# CellCircuit.net
KiCad netlist of a schematic drawn in Altium Designer
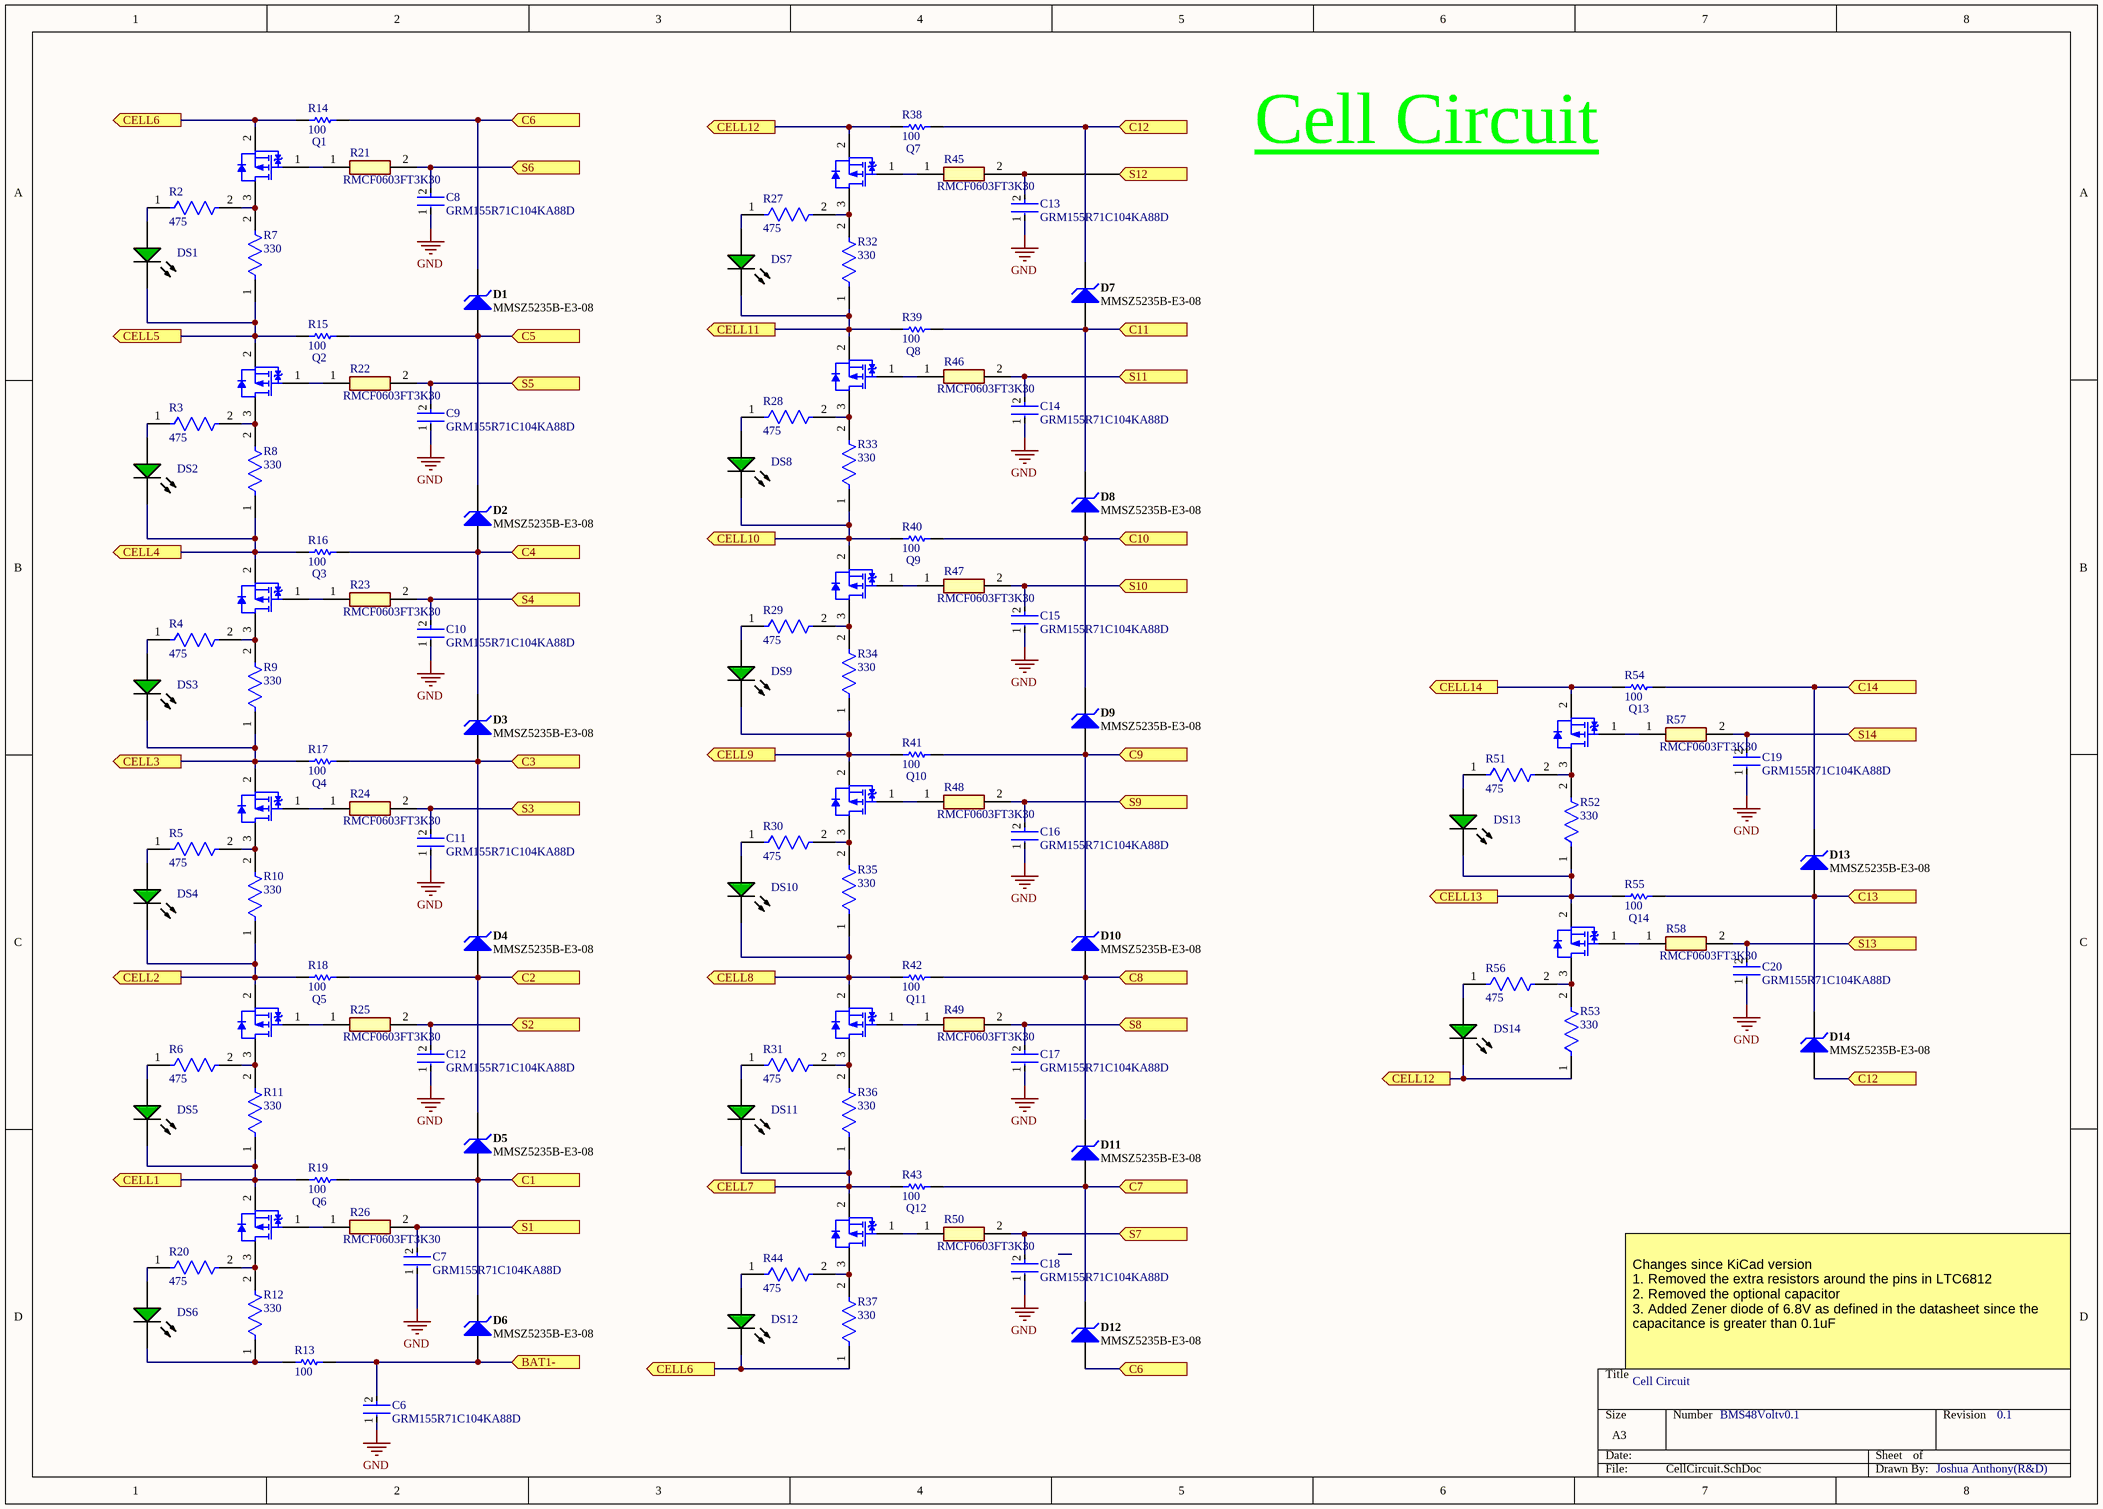
[diagram p0: CellCircuit.SchDoc]

(export (version "E")
  (design (tool "Eeschema 10.0.6"))
  (components
    (comp (ref "C6")
      (value "GRM155R71C104KA88D")
      (footprint "FP-GRM15-MFG")
      (description "CAP CER 0.1UF 16V X7R 0402")
      (fields
        (field (name "TOLERANCE") "10%")
        (field (name "OCTOPART") "https://octopart.com/grm155r71c104ka88d-murata-196880")
      )
      (libsource (lib "Altium Content Vault") (part "236180d848d6139a670b325ea6854c9"))
    )
    (comp (ref "C7")
      (value "GRM155R71C104KA88D")
      (footprint "FP-GRM15-MFG")
      (description "CAP CER 0.1UF 16V X7R 0402")
      (fields
        (field (name "TOLERANCE") "10%")
        (field (name "OCTOPART") "https://octopart.com/grm155r71c104ka88d-murata-196880")
      )
      (libsource (lib "Altium Content Vault") (part "236180d848d6139a670b325ea6854c9"))
    )
    (comp (ref "C8")
      (value "GRM155R71C104KA88D")
      (footprint "FP-GRM15-MFG")
      (description "CAP CER 0.1UF 16V X7R 0402")
      (fields
        (field (name "TOLERANCE") "10%")
        (field (name "OCTOPART") "https://octopart.com/grm155r71c104ka88d-murata-196880")
      )
      (libsource (lib "Altium Content Vault") (part "236180d848d6139a670b325ea6854c9"))
    )
    (comp (ref "C9")
      (value "GRM155R71C104KA88D")
      (footprint "FP-GRM15-MFG")
      (description "CAP CER 0.1UF 16V X7R 0402")
      (fields
        (field (name "TOLERANCE") "10%")
        (field (name "OCTOPART") "https://octopart.com/grm155r71c104ka88d-murata-196880")
      )
      (libsource (lib "Altium Content Vault") (part "236180d848d6139a670b325ea6854c9"))
    )
    (comp (ref "C10")
      (value "GRM155R71C104KA88D")
      (footprint "FP-GRM15-MFG")
      (description "CAP CER 0.1UF 16V X7R 0402")
      (fields
        (field (name "TOLERANCE") "10%")
        (field (name "OCTOPART") "https://octopart.com/grm155r71c104ka88d-murata-196880")
      )
      (libsource (lib "Altium Content Vault") (part "236180d848d6139a670b325ea6854c9"))
    )
    (comp (ref "C11")
      (value "GRM155R71C104KA88D")
      (footprint "FP-GRM15-MFG")
      (description "CAP CER 0.1UF 16V X7R 0402")
      (fields
        (field (name "TOLERANCE") "10%")
        (field (name "OCTOPART") "https://octopart.com/grm155r71c104ka88d-murata-196880")
      )
      (libsource (lib "Altium Content Vault") (part "236180d848d6139a670b325ea6854c9"))
    )
    (comp (ref "C12")
      (value "GRM155R71C104KA88D")
      (footprint "FP-GRM15-MFG")
      (description "CAP CER 0.1UF 16V X7R 0402")
      (fields
        (field (name "TOLERANCE") "10%")
        (field (name "OCTOPART") "https://octopart.com/grm155r71c104ka88d-murata-196880")
      )
      (libsource (lib "Altium Content Vault") (part "236180d848d6139a670b325ea6854c9"))
    )
    (comp (ref "C13")
      (value "GRM155R71C104KA88D")
      (footprint "FP-GRM15-MFG")
      (description "CAP CER 0.1UF 16V X7R 0402")
      (fields
        (field (name "TOLERANCE") "10%")
        (field (name "OCTOPART") "https://octopart.com/grm155r71c104ka88d-murata-196880")
      )
      (libsource (lib "Altium Content Vault") (part "236180d848d6139a670b325ea6854c9"))
    )
    (comp (ref "C14")
      (value "GRM155R71C104KA88D")
      (footprint "FP-GRM15-MFG")
      (description "CAP CER 0.1UF 16V X7R 0402")
      (fields
        (field (name "TOLERANCE") "10%")
        (field (name "OCTOPART") "https://octopart.com/grm155r71c104ka88d-murata-196880")
      )
      (libsource (lib "Altium Content Vault") (part "236180d848d6139a670b325ea6854c9"))
    )
    (comp (ref "C15")
      (value "GRM155R71C104KA88D")
      (footprint "FP-GRM15-MFG")
      (description "CAP CER 0.1UF 16V X7R 0402")
      (fields
        (field (name "TOLERANCE") "10%")
        (field (name "OCTOPART") "https://octopart.com/grm155r71c104ka88d-murata-196880")
      )
      (libsource (lib "Altium Content Vault") (part "236180d848d6139a670b325ea6854c9"))
    )
    (comp (ref "C16")
      (value "GRM155R71C104KA88D")
      (footprint "FP-GRM15-MFG")
      (description "CAP CER 0.1UF 16V X7R 0402")
      (fields
        (field (name "TOLERANCE") "10%")
        (field (name "OCTOPART") "https://octopart.com/grm155r71c104ka88d-murata-196880")
      )
      (libsource (lib "Altium Content Vault") (part "236180d848d6139a670b325ea6854c9"))
    )
    (comp (ref "C17")
      (value "GRM155R71C104KA88D")
      (footprint "FP-GRM15-MFG")
      (description "CAP CER 0.1UF 16V X7R 0402")
      (fields
        (field (name "TOLERANCE") "10%")
        (field (name "OCTOPART") "https://octopart.com/grm155r71c104ka88d-murata-196880")
      )
      (libsource (lib "Altium Content Vault") (part "236180d848d6139a670b325ea6854c9"))
    )
    (comp (ref "C18")
      (value "GRM155R71C104KA88D")
      (footprint "FP-GRM15-MFG")
      (description "CAP CER 0.1UF 16V X7R 0402")
      (fields
        (field (name "TOLERANCE") "10%")
        (field (name "OCTOPART") "https://octopart.com/grm155r71c104ka88d-murata-196880")
      )
      (libsource (lib "Altium Content Vault") (part "236180d848d6139a670b325ea6854c9"))
    )
    (comp (ref "C19")
      (value "GRM155R71C104KA88D")
      (footprint "FP-GRM15-MFG")
      (description "CAP CER 0.1UF 16V X7R 0402")
      (fields
        (field (name "TOLERANCE") "10%")
        (field (name "OCTOPART") "https://octopart.com/grm155r71c104ka88d-murata-196880")
      )
      (libsource (lib "Altium Content Vault") (part "236180d848d6139a670b325ea6854c9"))
    )
    (comp (ref "C20")
      (value "GRM155R71C104KA88D")
      (footprint "FP-GRM15-MFG")
      (description "CAP CER 0.1UF 16V X7R 0402")
      (fields
        (field (name "TOLERANCE") "10%")
        (field (name "OCTOPART") "https://octopart.com/grm155r71c104ka88d-murata-196880")
      )
      (libsource (lib "Altium Content Vault") (part "236180d848d6139a670b325ea6854c9"))
    )
    (comp (ref "D1")
      (value "MMSZ5235B-E3-08")
      (footprint "VISH-SOD-123-2_V")
      (description "Small Signal Zener Diode, 6.8 V +/- 5%, -55 to 155 degC, 2-Pin SOD-123, RoHS, Tape and Reel")
      (fields (field (name "MANUFACTURER") "Vishay Semiconductor") (field (name "TOLERANCE") "+/- 5%"))
      (libsource (lib "Altium Content Vault") (part "VISH-DZEN_A1K2-2"))
    )
    (comp (ref "D2")
      (value "MMSZ5235B-E3-08")
      (footprint "VISH-SOD-123-2_V")
      (description "Small Signal Zener Diode, 6.8 V +/- 5%, -55 to 155 degC, 2-Pin SOD-123, RoHS, Tape and Reel")
      (fields (field (name "MANUFACTURER") "Vishay Semiconductor") (field (name "TOLERANCE") "+/- 5%"))
      (libsource (lib "Altium Content Vault") (part "VISH-DZEN_A1K2-2"))
    )
    (comp (ref "D3")
      (value "MMSZ5235B-E3-08")
      (footprint "VISH-SOD-123-2_V")
      (description "Small Signal Zener Diode, 6.8 V +/- 5%, -55 to 155 degC, 2-Pin SOD-123, RoHS, Tape and Reel")
      (fields (field (name "MANUFACTURER") "Vishay Semiconductor") (field (name "TOLERANCE") "+/- 5%"))
      (libsource (lib "Altium Content Vault") (part "VISH-DZEN_A1K2-2"))
    )
    (comp (ref "D4")
      (value "MMSZ5235B-E3-08")
      (footprint "VISH-SOD-123-2_V")
      (description "Small Signal Zener Diode, 6.8 V +/- 5%, -55 to 155 degC, 2-Pin SOD-123, RoHS, Tape and Reel")
      (fields (field (name "MANUFACTURER") "Vishay Semiconductor") (field (name "TOLERANCE") "+/- 5%"))
      (libsource (lib "Altium Content Vault") (part "VISH-DZEN_A1K2-2"))
    )
    (comp (ref "D5")
      (value "MMSZ5235B-E3-08")
      (footprint "VISH-SOD-123-2_V")
      (description "Small Signal Zener Diode, 6.8 V +/- 5%, -55 to 155 degC, 2-Pin SOD-123, RoHS, Tape and Reel")
      (fields (field (name "MANUFACTURER") "Vishay Semiconductor") (field (name "TOLERANCE") "+/- 5%"))
      (libsource (lib "Altium Content Vault") (part "VISH-DZEN_A1K2-2"))
    )
    (comp (ref "D6")
      (value "MMSZ5235B-E3-08")
      (footprint "VISH-SOD-123-2_V")
      (description "Small Signal Zener Diode, 6.8 V +/- 5%, -55 to 155 degC, 2-Pin SOD-123, RoHS, Tape and Reel")
      (fields (field (name "MANUFACTURER") "Vishay Semiconductor") (field (name "TOLERANCE") "+/- 5%"))
      (libsource (lib "Altium Content Vault") (part "VISH-DZEN_A1K2-2"))
    )
    (comp (ref "D7")
      (value "MMSZ5235B-E3-08")
      (footprint "VISH-SOD-123-2_V")
      (description "Small Signal Zener Diode, 6.8 V +/- 5%, -55 to 155 degC, 2-Pin SOD-123, RoHS, Tape and Reel")
      (fields (field (name "MANUFACTURER") "Vishay Semiconductor") (field (name "TOLERANCE") "+/- 5%"))
      (libsource (lib "Altium Content Vault") (part "VISH-DZEN_A1K2-2"))
    )
    (comp (ref "D8")
      (value "MMSZ5235B-E3-08")
      (footprint "VISH-SOD-123-2_V")
      (description "Small Signal Zener Diode, 6.8 V +/- 5%, -55 to 155 degC, 2-Pin SOD-123, RoHS, Tape and Reel")
      (fields (field (name "MANUFACTURER") "Vishay Semiconductor") (field (name "TOLERANCE") "+/- 5%"))
      (libsource (lib "Altium Content Vault") (part "VISH-DZEN_A1K2-2"))
    )
    (comp (ref "D9")
      (value "MMSZ5235B-E3-08")
      (footprint "VISH-SOD-123-2_V")
      (description "Small Signal Zener Diode, 6.8 V +/- 5%, -55 to 155 degC, 2-Pin SOD-123, RoHS, Tape and Reel")
      (fields (field (name "MANUFACTURER") "Vishay Semiconductor") (field (name "TOLERANCE") "+/- 5%"))
      (libsource (lib "Altium Content Vault") (part "VISH-DZEN_A1K2-2"))
    )
    (comp (ref "D10")
      (value "MMSZ5235B-E3-08")
      (footprint "VISH-SOD-123-2_V")
      (description "Small Signal Zener Diode, 6.8 V +/- 5%, -55 to 155 degC, 2-Pin SOD-123, RoHS, Tape and Reel")
      (fields (field (name "MANUFACTURER") "Vishay Semiconductor") (field (name "TOLERANCE") "+/- 5%"))
      (libsource (lib "Altium Content Vault") (part "VISH-DZEN_A1K2-2"))
    )
    (comp (ref "D11")
      (value "MMSZ5235B-E3-08")
      (footprint "VISH-SOD-123-2_V")
      (description "Small Signal Zener Diode, 6.8 V +/- 5%, -55 to 155 degC, 2-Pin SOD-123, RoHS, Tape and Reel")
      (fields (field (name "MANUFACTURER") "Vishay Semiconductor") (field (name "TOLERANCE") "+/- 5%"))
      (libsource (lib "Altium Content Vault") (part "VISH-DZEN_A1K2-2"))
    )
    (comp (ref "D12")
      (value "MMSZ5235B-E3-08")
      (footprint "VISH-SOD-123-2_V")
      (description "Small Signal Zener Diode, 6.8 V +/- 5%, -55 to 155 degC, 2-Pin SOD-123, RoHS, Tape and Reel")
      (fields (field (name "MANUFACTURER") "Vishay Semiconductor") (field (name "TOLERANCE") "+/- 5%"))
      (libsource (lib "Altium Content Vault") (part "VISH-DZEN_A1K2-2"))
    )
    (comp (ref "D13")
      (value "MMSZ5235B-E3-08")
      (footprint "VISH-SOD-123-2_V")
      (description "Small Signal Zener Diode, 6.8 V +/- 5%, -55 to 155 degC, 2-Pin SOD-123, RoHS, Tape and Reel")
      (fields (field (name "MANUFACTURER") "Vishay Semiconductor") (field (name "TOLERANCE") "+/- 5%"))
      (libsource (lib "Altium Content Vault") (part "VISH-DZEN_A1K2-2"))
    )
    (comp (ref "D14")
      (value "MMSZ5235B-E3-08")
      (footprint "VISH-SOD-123-2_V")
      (description "Small Signal Zener Diode, 6.8 V +/- 5%, -55 to 155 degC, 2-Pin SOD-123, RoHS, Tape and Reel")
      (fields (field (name "MANUFACTURER") "Vishay Semiconductor") (field (name "TOLERANCE") "+/- 5%"))
      (libsource (lib "Altium Content Vault") (part "VISH-DZEN_A1K2-2"))
    )
    (comp (ref "DS1")
      (value "HSMG-C170")
      (footprint "AVAG-HSMX-C170_V")
      (description "Chip LED, Green, 2.2 V, -40 to 85 degC, 2-Pin SMD, Pb-Free, Tape and Reel")
      (fields (field (name "MANUFACTURER") "Avago"))
      (libsource (lib "Altium Content Vault") (part "LED_GREEN_A1K2-2"))
    )
    (comp (ref "DS2")
      (value "HSMG-C170")
      (footprint "AVAG-HSMX-C170_V")
      (description "Chip LED, Green, 2.2 V, -40 to 85 degC, 2-Pin SMD, Pb-Free, Tape and Reel")
      (fields (field (name "MANUFACTURER") "Avago"))
      (libsource (lib "Altium Content Vault") (part "LED_GREEN_A1K2-2"))
    )
    (comp (ref "DS3")
      (value "HSMG-C170")
      (footprint "AVAG-HSMX-C170_V")
      (description "Chip LED, Green, 2.2 V, -40 to 85 degC, 2-Pin SMD, Pb-Free, Tape and Reel")
      (fields (field (name "MANUFACTURER") "Avago"))
      (libsource (lib "Altium Content Vault") (part "LED_GREEN_A1K2-2"))
    )
    (comp (ref "DS4")
      (value "HSMG-C170")
      (footprint "AVAG-HSMX-C170_V")
      (description "Chip LED, Green, 2.2 V, -40 to 85 degC, 2-Pin SMD, Pb-Free, Tape and Reel")
      (fields (field (name "MANUFACTURER") "Avago"))
      (libsource (lib "Altium Content Vault") (part "LED_GREEN_A1K2-2"))
    )
    (comp (ref "DS5")
      (value "HSMG-C170")
      (footprint "AVAG-HSMX-C170_V")
      (description "Chip LED, Green, 2.2 V, -40 to 85 degC, 2-Pin SMD, Pb-Free, Tape and Reel")
      (fields (field (name "MANUFACTURER") "Avago"))
      (libsource (lib "Altium Content Vault") (part "LED_GREEN_A1K2-2"))
    )
    (comp (ref "DS6")
      (value "HSMG-C170")
      (footprint "AVAG-HSMX-C170_V")
      (description "Chip LED, Green, 2.2 V, -40 to 85 degC, 2-Pin SMD, Pb-Free, Tape and Reel")
      (fields (field (name "MANUFACTURER") "Avago"))
      (libsource (lib "Altium Content Vault") (part "LED_GREEN_A1K2-2"))
    )
    (comp (ref "DS7")
      (value "HSMG-C170")
      (footprint "AVAG-HSMX-C170_V")
      (description "Chip LED, Green, 2.2 V, -40 to 85 degC, 2-Pin SMD, Pb-Free, Tape and Reel")
      (fields (field (name "MANUFACTURER") "Avago"))
      (libsource (lib "Altium Content Vault") (part "LED_GREEN_A1K2-2"))
    )
    (comp (ref "DS8")
      (value "HSMG-C170")
      (footprint "AVAG-HSMX-C170_V")
      (description "Chip LED, Green, 2.2 V, -40 to 85 degC, 2-Pin SMD, Pb-Free, Tape and Reel")
      (fields (field (name "MANUFACTURER") "Avago"))
      (libsource (lib "Altium Content Vault") (part "LED_GREEN_A1K2-2"))
    )
    (comp (ref "DS9")
      (value "HSMG-C170")
      (footprint "AVAG-HSMX-C170_V")
      (description "Chip LED, Green, 2.2 V, -40 to 85 degC, 2-Pin SMD, Pb-Free, Tape and Reel")
      (fields (field (name "MANUFACTURER") "Avago"))
      (libsource (lib "Altium Content Vault") (part "LED_GREEN_A1K2-2"))
    )
    (comp (ref "DS10")
      (value "HSMG-C170")
      (footprint "AVAG-HSMX-C170_V")
      (description "Chip LED, Green, 2.2 V, -40 to 85 degC, 2-Pin SMD, Pb-Free, Tape and Reel")
      (fields (field (name "MANUFACTURER") "Avago"))
      (libsource (lib "Altium Content Vault") (part "LED_GREEN_A1K2-2"))
    )
    (comp (ref "DS11")
      (value "HSMG-C170")
      (footprint "AVAG-HSMX-C170_V")
      (description "Chip LED, Green, 2.2 V, -40 to 85 degC, 2-Pin SMD, Pb-Free, Tape and Reel")
      (fields (field (name "MANUFACTURER") "Avago"))
      (libsource (lib "Altium Content Vault") (part "LED_GREEN_A1K2-2"))
    )
    (comp (ref "DS12")
      (value "HSMG-C170")
      (footprint "AVAG-HSMX-C170_V")
      (description "Chip LED, Green, 2.2 V, -40 to 85 degC, 2-Pin SMD, Pb-Free, Tape and Reel")
      (fields (field (name "MANUFACTURER") "Avago"))
      (libsource (lib "Altium Content Vault") (part "LED_GREEN_A1K2-2"))
    )
    (comp (ref "DS13")
      (value "HSMG-C170")
      (footprint "AVAG-HSMX-C170_V")
      (description "Chip LED, Green, 2.2 V, -40 to 85 degC, 2-Pin SMD, Pb-Free, Tape and Reel")
      (fields (field (name "MANUFACTURER") "Avago"))
      (libsource (lib "Altium Content Vault") (part "LED_GREEN_A1K2-2"))
    )
    (comp (ref "DS14")
      (value "HSMG-C170")
      (footprint "AVAG-HSMX-C170_V")
      (description "Chip LED, Green, 2.2 V, -40 to 85 degC, 2-Pin SMD, Pb-Free, Tape and Reel")
      (fields (field (name "MANUFACTURER") "Avago"))
      (libsource (lib "Altium Content Vault") (part "LED_GREEN_A1K2-2"))
    )
    (comp (ref "Q1")
      (value "BSS308PE")
      (footprint "INF-PG-SOT23_L")
      (fields (field (name "MANUFACTURER") "Infineon"))
      (libsource (lib "Altium Content Vault") (part "INF-BSS3XXPE-PG-SOT23-3"))
    )
    (comp (ref "Q2")
      (value "BSS308PE")
      (footprint "INF-PG-SOT23_L")
      (fields (field (name "MANUFACTURER") "Infineon"))
      (libsource (lib "Altium Content Vault") (part "INF-BSS3XXPE-PG-SOT23-3"))
    )
    (comp (ref "Q3")
      (value "BSS308PE")
      (footprint "INF-PG-SOT23_L")
      (fields (field (name "MANUFACTURER") "Infineon"))
      (libsource (lib "Altium Content Vault") (part "INF-BSS3XXPE-PG-SOT23-3"))
    )
    (comp (ref "Q4")
      (value "BSS308PE")
      (footprint "INF-PG-SOT23_L")
      (fields (field (name "MANUFACTURER") "Infineon"))
      (libsource (lib "Altium Content Vault") (part "INF-BSS3XXPE-PG-SOT23-3"))
    )
    (comp (ref "Q5")
      (value "BSS308PE")
      (footprint "INF-PG-SOT23_L")
      (fields (field (name "MANUFACTURER") "Infineon"))
      (libsource (lib "Altium Content Vault") (part "INF-BSS3XXPE-PG-SOT23-3"))
    )
    (comp (ref "Q6")
      (value "BSS308PE")
      (footprint "INF-PG-SOT23_L")
      (fields (field (name "MANUFACTURER") "Infineon"))
      (libsource (lib "Altium Content Vault") (part "INF-BSS3XXPE-PG-SOT23-3"))
    )
    (comp (ref "Q7")
      (value "BSS308PE")
      (footprint "INF-PG-SOT23_L")
      (fields (field (name "MANUFACTURER") "Infineon"))
      (libsource (lib "Altium Content Vault") (part "INF-BSS3XXPE-PG-SOT23-3"))
    )
    (comp (ref "Q8")
      (value "BSS308PE")
      (footprint "INF-PG-SOT23_L")
      (fields (field (name "MANUFACTURER") "Infineon"))
      (libsource (lib "Altium Content Vault") (part "INF-BSS3XXPE-PG-SOT23-3"))
    )
    (comp (ref "Q9")
      (value "BSS308PE")
      (footprint "INF-PG-SOT23_L")
      (fields (field (name "MANUFACTURER") "Infineon"))
      (libsource (lib "Altium Content Vault") (part "INF-BSS3XXPE-PG-SOT23-3"))
    )
    (comp (ref "Q10")
      (value "BSS308PE")
      (footprint "INF-PG-SOT23_L")
      (fields (field (name "MANUFACTURER") "Infineon"))
      (libsource (lib "Altium Content Vault") (part "INF-BSS3XXPE-PG-SOT23-3"))
    )
    (comp (ref "Q11")
      (value "BSS308PE")
      (footprint "INF-PG-SOT23_L")
      (fields (field (name "MANUFACTURER") "Infineon"))
      (libsource (lib "Altium Content Vault") (part "INF-BSS3XXPE-PG-SOT23-3"))
    )
    (comp (ref "Q12")
      (value "BSS308PE")
      (footprint "INF-PG-SOT23_L")
      (fields (field (name "MANUFACTURER") "Infineon"))
      (libsource (lib "Altium Content Vault") (part "INF-BSS3XXPE-PG-SOT23-3"))
    )
    (comp (ref "Q13")
      (value "BSS308PE")
      (footprint "INF-PG-SOT23_L")
      (fields (field (name "MANUFACTURER") "Infineon"))
      (libsource (lib "Altium Content Vault") (part "INF-BSS3XXPE-PG-SOT23-3"))
    )
    (comp (ref "Q14")
      (value "BSS308PE")
      (footprint "INF-PG-SOT23_L")
      (fields (field (name "MANUFACTURER") "Infineon"))
      (libsource (lib "Altium Content Vault") (part "INF-BSS3XXPE-PG-SOT23-3"))
    )
    (comp (ref "R2")
      (value "475")
      (footprint "FP-CR0603-MFG")
      (description "Thick Film Chip Resistors 0603 475Ω 0.1W 1% 100ppm/°C")
      (fields (field (name "TOLERANCE") "1%"))
      (libsource (lib "Altium Content Vault") (part "1029c3af85768c4190bb7ad29bc67b5"))
    )
    (comp (ref "R3")
      (value "475")
      (footprint "FP-CR0603-MFG")
      (description "Thick Film Chip Resistors 0603 475Ω 0.1W 1% 100ppm/°C")
      (fields (field (name "TOLERANCE") "1%"))
      (libsource (lib "Altium Content Vault") (part "1029c3af85768c4190bb7ad29bc67b5"))
    )
    (comp (ref "R4")
      (value "475")
      (footprint "FP-CR0603-MFG")
      (description "Thick Film Chip Resistors 0603 475Ω 0.1W 1% 100ppm/°C")
      (fields (field (name "TOLERANCE") "1%"))
      (libsource (lib "Altium Content Vault") (part "1029c3af85768c4190bb7ad29bc67b5"))
    )
    (comp (ref "R5")
      (value "475")
      (footprint "FP-CR0603-MFG")
      (description "Thick Film Chip Resistors 0603 475Ω 0.1W 1% 100ppm/°C")
      (fields (field (name "TOLERANCE") "1%"))
      (libsource (lib "Altium Content Vault") (part "1029c3af85768c4190bb7ad29bc67b5"))
    )
    (comp (ref "R6")
      (value "475")
      (footprint "FP-CR0603-MFG")
      (description "Thick Film Chip Resistors 0603 475Ω 0.1W 1% 100ppm/°C")
      (fields (field (name "TOLERANCE") "1%"))
      (libsource (lib "Altium Content Vault") (part "1029c3af85768c4190bb7ad29bc67b5"))
    )
    (comp (ref "R7")
      (value "330")
      (footprint "FP-CRCW0603-e3-MFG")
      (description "RES Thick Film, 330Ω, 1%, 0.1W, 100ppm/°C, 0603")
      (fields (field (name "TOLERANCE") "1%"))
      (libsource (lib "Altium Content Vault") (part "1029c3af85768c4190bb7ad29bc67b5"))
    )
    (comp (ref "R8")
      (value "330")
      (footprint "FP-CRCW0603-e3-MFG")
      (description "RES Thick Film, 330Ω, 1%, 0.1W, 100ppm/°C, 0603")
      (fields (field (name "TOLERANCE") "1%"))
      (libsource (lib "Altium Content Vault") (part "1029c3af85768c4190bb7ad29bc67b5"))
    )
    (comp (ref "R9")
      (value "330")
      (footprint "FP-CRCW0603-e3-MFG")
      (description "RES Thick Film, 330Ω, 1%, 0.1W, 100ppm/°C, 0603")
      (fields (field (name "TOLERANCE") "1%"))
      (libsource (lib "Altium Content Vault") (part "1029c3af85768c4190bb7ad29bc67b5"))
    )
    (comp (ref "R10")
      (value "330")
      (footprint "FP-CRCW0603-e3-MFG")
      (description "RES Thick Film, 330Ω, 1%, 0.1W, 100ppm/°C, 0603")
      (fields (field (name "TOLERANCE") "1%"))
      (libsource (lib "Altium Content Vault") (part "1029c3af85768c4190bb7ad29bc67b5"))
    )
    (comp (ref "R11")
      (value "330")
      (footprint "FP-CRCW0603-e3-MFG")
      (description "RES Thick Film, 330Ω, 1%, 0.1W, 100ppm/°C, 0603")
      (fields (field (name "TOLERANCE") "1%"))
      (libsource (lib "Altium Content Vault") (part "1029c3af85768c4190bb7ad29bc67b5"))
    )
    (comp (ref "R12")
      (value "330")
      (footprint "FP-CRCW0603-e3-MFG")
      (description "RES Thick Film, 330Ω, 1%, 0.1W, 100ppm/°C, 0603")
      (fields (field (name "TOLERANCE") "1%"))
      (libsource (lib "Altium Content Vault") (part "1029c3af85768c4190bb7ad29bc67b5"))
    )
    (comp (ref "R13")
      (value "100")
      (footprint "RESC1005X40X25LL05T05")
      (description "Chip Resistor, 100 Ohm, +/- 1%, 100 mW, -55 to 155 degC, 0402 (1005 Metric), RoHS, Tape and Reel")
      (fields (field (name "MANUFACTURER") "Basic Passives") (field (name "TOLERANCE") "1%"))
      (libsource (lib "Altium Content Vault") (part "RES-2"))
    )
    (comp (ref "R14")
      (value "100")
      (footprint "RESC1005X40X25LL05T05")
      (description "Chip Resistor, 100 Ohm, +/- 1%, 100 mW, -55 to 155 degC, 0402 (1005 Metric), RoHS, Tape and Reel")
      (fields (field (name "MANUFACTURER") "Basic Passives") (field (name "TOLERANCE") "1%"))
      (libsource (lib "Altium Content Vault") (part "RES-2"))
    )
    (comp (ref "R15")
      (value "100")
      (footprint "RESC1005X40X25LL05T05")
      (description "Chip Resistor, 100 Ohm, +/- 1%, 100 mW, -55 to 155 degC, 0402 (1005 Metric), RoHS, Tape and Reel")
      (fields (field (name "MANUFACTURER") "Basic Passives") (field (name "TOLERANCE") "1%"))
      (libsource (lib "Altium Content Vault") (part "RES-2"))
    )
    (comp (ref "R16")
      (value "100")
      (footprint "RESC1005X40X25LL05T05")
      (description "Chip Resistor, 100 Ohm, +/- 1%, 100 mW, -55 to 155 degC, 0402 (1005 Metric), RoHS, Tape and Reel")
      (fields (field (name "MANUFACTURER") "Basic Passives") (field (name "TOLERANCE") "1%"))
      (libsource (lib "Altium Content Vault") (part "RES-2"))
    )
    (comp (ref "R17")
      (value "100")
      (footprint "RESC1005X40X25LL05T05")
      (description "Chip Resistor, 100 Ohm, +/- 1%, 100 mW, -55 to 155 degC, 0402 (1005 Metric), RoHS, Tape and Reel")
      (fields (field (name "MANUFACTURER") "Basic Passives") (field (name "TOLERANCE") "1%"))
      (libsource (lib "Altium Content Vault") (part "RES-2"))
    )
    (comp (ref "R18")
      (value "100")
      (footprint "RESC1005X40X25LL05T05")
      (description "Chip Resistor, 100 Ohm, +/- 1%, 100 mW, -55 to 155 degC, 0402 (1005 Metric), RoHS, Tape and Reel")
      (fields (field (name "MANUFACTURER") "Basic Passives") (field (name "TOLERANCE") "1%"))
      (libsource (lib "Altium Content Vault") (part "RES-2"))
    )
    (comp (ref "R19")
      (value "100")
      (footprint "RESC1005X40X25LL05T05")
      (description "Chip Resistor, 100 Ohm, +/- 1%, 100 mW, -55 to 155 degC, 0402 (1005 Metric), RoHS, Tape and Reel")
      (fields (field (name "MANUFACTURER") "Basic Passives") (field (name "TOLERANCE") "1%"))
      (libsource (lib "Altium Content Vault") (part "RES-2"))
    )
    (comp (ref "R20")
      (value "475")
      (footprint "FP-CR0603-MFG")
      (description "Thick Film Chip Resistors 0603 475Ω 0.1W 1% 100ppm/°C")
      (fields (field (name "TOLERANCE") "1%"))
      (libsource (lib "Altium Content Vault") (part "1029c3af85768c4190bb7ad29bc67b5"))
    )
    (comp (ref "R21")
      (value "RMCF0603FT3K30")
      (footprint "SamacSys:RESC1608X55N")
      (description "Resistor")
      (libsource (lib "*") (part "RMCF0603FT3K30"))
    )
    (comp (ref "R22")
      (value "RMCF0603FT3K30")
      (footprint "SamacSys:RESC1608X55N")
      (description "Resistor")
      (libsource (lib "*") (part "RMCF0603FT3K30"))
    )
    (comp (ref "R23")
      (value "RMCF0603FT3K30")
      (footprint "SamacSys:RESC1608X55N")
      (description "Resistor")
      (libsource (lib "*") (part "RMCF0603FT3K30"))
    )
    (comp (ref "R24")
      (value "RMCF0603FT3K30")
      (footprint "SamacSys:RESC1608X55N")
      (description "Resistor")
      (libsource (lib "*") (part "RMCF0603FT3K30"))
    )
    (comp (ref "R25")
      (value "RMCF0603FT3K30")
      (footprint "SamacSys:RESC1608X55N")
      (description "Resistor")
      (libsource (lib "*") (part "RMCF0603FT3K30"))
    )
    (comp (ref "R26")
      (value "RMCF0603FT3K30")
      (footprint "SamacSys:RESC1608X55N")
      (description "Resistor")
      (libsource (lib "*") (part "RMCF0603FT3K30"))
    )
    (comp (ref "R27")
      (value "475")
      (footprint "FP-CR0603-MFG")
      (description "Thick Film Chip Resistors 0603 475Ω 0.1W 1% 100ppm/°C")
      (fields (field (name "TOLERANCE") "1%"))
      (libsource (lib "Altium Content Vault") (part "1029c3af85768c4190bb7ad29bc67b5"))
    )
    (comp (ref "R28")
      (value "475")
      (footprint "FP-CR0603-MFG")
      (description "Thick Film Chip Resistors 0603 475Ω 0.1W 1% 100ppm/°C")
      (fields (field (name "TOLERANCE") "1%"))
      (libsource (lib "Altium Content Vault") (part "1029c3af85768c4190bb7ad29bc67b5"))
    )
    (comp (ref "R29")
      (value "475")
      (footprint "FP-CR0603-MFG")
      (description "Thick Film Chip Resistors 0603 475Ω 0.1W 1% 100ppm/°C")
      (fields (field (name "TOLERANCE") "1%"))
      (libsource (lib "Altium Content Vault") (part "1029c3af85768c4190bb7ad29bc67b5"))
    )
    (comp (ref "R30")
      (value "475")
      (footprint "FP-CR0603-MFG")
      (description "Thick Film Chip Resistors 0603 475Ω 0.1W 1% 100ppm/°C")
      (fields (field (name "TOLERANCE") "1%"))
      (libsource (lib "Altium Content Vault") (part "1029c3af85768c4190bb7ad29bc67b5"))
    )
    (comp (ref "R31")
      (value "475")
      (footprint "FP-CR0603-MFG")
      (description "Thick Film Chip Resistors 0603 475Ω 0.1W 1% 100ppm/°C")
      (fields (field (name "TOLERANCE") "1%"))
      (libsource (lib "Altium Content Vault") (part "1029c3af85768c4190bb7ad29bc67b5"))
    )
    (comp (ref "R32")
      (value "330")
      (footprint "FP-CRCW0603-e3-MFG")
      (description "RES Thick Film, 330Ω, 1%, 0.1W, 100ppm/°C, 0603")
      (fields (field (name "TOLERANCE") "1%"))
      (libsource (lib "Altium Content Vault") (part "1029c3af85768c4190bb7ad29bc67b5"))
    )
    (comp (ref "R33")
      (value "330")
      (footprint "FP-CRCW0603-e3-MFG")
      (description "RES Thick Film, 330Ω, 1%, 0.1W, 100ppm/°C, 0603")
      (fields (field (name "TOLERANCE") "1%"))
      (libsource (lib "Altium Content Vault") (part "1029c3af85768c4190bb7ad29bc67b5"))
    )
    (comp (ref "R34")
      (value "330")
      (footprint "FP-CRCW0603-e3-MFG")
      (description "RES Thick Film, 330Ω, 1%, 0.1W, 100ppm/°C, 0603")
      (fields (field (name "TOLERANCE") "1%"))
      (libsource (lib "Altium Content Vault") (part "1029c3af85768c4190bb7ad29bc67b5"))
    )
    (comp (ref "R35")
      (value "330")
      (footprint "FP-CRCW0603-e3-MFG")
      (description "RES Thick Film, 330Ω, 1%, 0.1W, 100ppm/°C, 0603")
      (fields (field (name "TOLERANCE") "1%"))
      (libsource (lib "Altium Content Vault") (part "1029c3af85768c4190bb7ad29bc67b5"))
    )
    (comp (ref "R36")
      (value "330")
      (footprint "FP-CRCW0603-e3-MFG")
      (description "RES Thick Film, 330Ω, 1%, 0.1W, 100ppm/°C, 0603")
      (fields (field (name "TOLERANCE") "1%"))
      (libsource (lib "Altium Content Vault") (part "1029c3af85768c4190bb7ad29bc67b5"))
    )
    (comp (ref "R37")
      (value "330")
      (footprint "FP-CRCW0603-e3-MFG")
      (description "RES Thick Film, 330Ω, 1%, 0.1W, 100ppm/°C, 0603")
      (fields (field (name "TOLERANCE") "1%"))
      (libsource (lib "Altium Content Vault") (part "1029c3af85768c4190bb7ad29bc67b5"))
    )
    (comp (ref "R38")
      (value "100")
      (footprint "RESC1005X40X25LL05T05")
      (description "Chip Resistor, 100 Ohm, +/- 1%, 100 mW, -55 to 155 degC, 0402 (1005 Metric), RoHS, Tape and Reel")
      (fields (field (name "MANUFACTURER") "Basic Passives") (field (name "TOLERANCE") "1%"))
      (libsource (lib "Altium Content Vault") (part "RES-2"))
    )
    (comp (ref "R39")
      (value "100")
      (footprint "RESC1005X40X25LL05T05")
      (description "Chip Resistor, 100 Ohm, +/- 1%, 100 mW, -55 to 155 degC, 0402 (1005 Metric), RoHS, Tape and Reel")
      (fields (field (name "MANUFACTURER") "Basic Passives") (field (name "TOLERANCE") "1%"))
      (libsource (lib "Altium Content Vault") (part "RES-2"))
    )
    (comp (ref "R40")
      (value "100")
      (footprint "RESC1005X40X25LL05T05")
      (description "Chip Resistor, 100 Ohm, +/- 1%, 100 mW, -55 to 155 degC, 0402 (1005 Metric), RoHS, Tape and Reel")
      (fields (field (name "MANUFACTURER") "Basic Passives") (field (name "TOLERANCE") "1%"))
      (libsource (lib "Altium Content Vault") (part "RES-2"))
    )
    (comp (ref "R41")
      (value "100")
      (footprint "RESC1005X40X25LL05T05")
      (description "Chip Resistor, 100 Ohm, +/- 1%, 100 mW, -55 to 155 degC, 0402 (1005 Metric), RoHS, Tape and Reel")
      (fields (field (name "MANUFACTURER") "Basic Passives") (field (name "TOLERANCE") "1%"))
      (libsource (lib "Altium Content Vault") (part "RES-2"))
    )
    (comp (ref "R42")
      (value "100")
      (footprint "RESC1005X40X25LL05T05")
      (description "Chip Resistor, 100 Ohm, +/- 1%, 100 mW, -55 to 155 degC, 0402 (1005 Metric), RoHS, Tape and Reel")
      (fields (field (name "MANUFACTURER") "Basic Passives") (field (name "TOLERANCE") "1%"))
      (libsource (lib "Altium Content Vault") (part "RES-2"))
    )
    (comp (ref "R43")
      (value "100")
      (footprint "RESC1005X40X25LL05T05")
      (description "Chip Resistor, 100 Ohm, +/- 1%, 100 mW, -55 to 155 degC, 0402 (1005 Metric), RoHS, Tape and Reel")
      (fields (field (name "MANUFACTURER") "Basic Passives") (field (name "TOLERANCE") "1%"))
      (libsource (lib "Altium Content Vault") (part "RES-2"))
    )
    (comp (ref "R44")
      (value "475")
      (footprint "FP-CR0603-MFG")
      (description "Thick Film Chip Resistors 0603 475Ω 0.1W 1% 100ppm/°C")
      (fields (field (name "TOLERANCE") "1%"))
      (libsource (lib "Altium Content Vault") (part "1029c3af85768c4190bb7ad29bc67b5"))
    )
    (comp (ref "R45")
      (value "RMCF0603FT3K30")
      (footprint "SamacSys:RESC1608X55N")
      (description "Resistor")
      (libsource (lib "*") (part "RMCF0603FT3K30"))
    )
    (comp (ref "R46")
      (value "RMCF0603FT3K30")
      (footprint "SamacSys:RESC1608X55N")
      (description "Resistor")
      (libsource (lib "*") (part "RMCF0603FT3K30"))
    )
    (comp (ref "R47")
      (value "RMCF0603FT3K30")
      (footprint "SamacSys:RESC1608X55N")
      (description "Resistor")
      (libsource (lib "*") (part "RMCF0603FT3K30"))
    )
    (comp (ref "R48")
      (value "RMCF0603FT3K30")
      (footprint "SamacSys:RESC1608X55N")
      (description "Resistor")
      (libsource (lib "*") (part "RMCF0603FT3K30"))
    )
    (comp (ref "R49")
      (value "RMCF0603FT3K30")
      (footprint "SamacSys:RESC1608X55N")
      (description "Resistor")
      (libsource (lib "*") (part "RMCF0603FT3K30"))
    )
    (comp (ref "R50")
      (value "RMCF0603FT3K30")
      (footprint "SamacSys:RESC1608X55N")
      (description "Resistor")
      (libsource (lib "*") (part "RMCF0603FT3K30"))
    )
    (comp (ref "R51")
      (value "475")
      (footprint "FP-CR0603-MFG")
      (description "Thick Film Chip Resistors 0603 475Ω 0.1W 1% 100ppm/°C")
      (fields (field (name "TOLERANCE") "1%"))
      (libsource (lib "Altium Content Vault") (part "1029c3af85768c4190bb7ad29bc67b5"))
    )
    (comp (ref "R52")
      (value "330")
      (footprint "FP-CRCW0603-e3-MFG")
      (description "RES Thick Film, 330Ω, 1%, 0.1W, 100ppm/°C, 0603")
      (fields (field (name "TOLERANCE") "1%"))
      (libsource (lib "Altium Content Vault") (part "1029c3af85768c4190bb7ad29bc67b5"))
    )
    (comp (ref "R53")
      (value "330")
      (footprint "FP-CRCW0603-e3-MFG")
      (description "RES Thick Film, 330Ω, 1%, 0.1W, 100ppm/°C, 0603")
      (fields (field (name "TOLERANCE") "1%"))
      (libsource (lib "Altium Content Vault") (part "1029c3af85768c4190bb7ad29bc67b5"))
    )
    (comp (ref "R54")
      (value "100")
      (footprint "RESC1005X40X25LL05T05")
      (description "Chip Resistor, 100 Ohm, +/- 1%, 100 mW, -55 to 155 degC, 0402 (1005 Metric), RoHS, Tape and Reel")
      (fields (field (name "MANUFACTURER") "Basic Passives") (field (name "TOLERANCE") "1%"))
      (libsource (lib "Altium Content Vault") (part "RES-2"))
    )
    (comp (ref "R55")
      (value "100")
      (footprint "RESC1005X40X25LL05T05")
      (description "Chip Resistor, 100 Ohm, +/- 1%, 100 mW, -55 to 155 degC, 0402 (1005 Metric), RoHS, Tape and Reel")
      (fields (field (name "MANUFACTURER") "Basic Passives") (field (name "TOLERANCE") "1%"))
      (libsource (lib "Altium Content Vault") (part "RES-2"))
    )
    (comp (ref "R56")
      (value "475")
      (footprint "FP-CR0603-MFG")
      (description "Thick Film Chip Resistors 0603 475Ω 0.1W 1% 100ppm/°C")
      (fields (field (name "TOLERANCE") "1%"))
      (libsource (lib "Altium Content Vault") (part "1029c3af85768c4190bb7ad29bc67b5"))
    )
    (comp (ref "R57")
      (value "RMCF0603FT3K30")
      (footprint "SamacSys:RESC1608X55N")
      (description "Resistor")
      (libsource (lib "*") (part "RMCF0603FT3K30"))
    )
    (comp (ref "R58")
      (value "RMCF0603FT3K30")
      (footprint "SamacSys:RESC1608X55N")
      (description "Resistor")
      (libsource (lib "*") (part "RMCF0603FT3K30"))
    )
  )
  (nets
    (net (code "1") (name "/BAT1-") (class "Default")
      (node (ref "C6") (pin "2") (pinfunction "2_2") (pintype "passive"))
      (node (ref "D6") (pin "1") (pinfunction "A_1") (pintype "passive"))
      (node (ref "R13") (pin "2") (pinfunction "2_2") (pintype "passive"))
    )
    (net (code "2") (name "/C1") (class "Default")
      (node (ref "D5") (pin "1") (pinfunction "A_1") (pintype "passive"))
      (node (ref "D6") (pin "2") (pinfunction "K_2") (pintype "passive"))
      (node (ref "R19") (pin "2") (pinfunction "2_2") (pintype "passive"))
    )
    (net (code "3") (name "/C2") (class "Default")
      (node (ref "D4") (pin "1") (pinfunction "A_1") (pintype "passive"))
      (node (ref "D5") (pin "2") (pinfunction "K_2") (pintype "passive"))
      (node (ref "R18") (pin "2") (pinfunction "2_2") (pintype "passive"))
    )
    (net (code "4") (name "/C3") (class "Default")
      (node (ref "D3") (pin "1") (pinfunction "A_1") (pintype "passive"))
      (node (ref "D4") (pin "2") (pinfunction "K_2") (pintype "passive"))
      (node (ref "R17") (pin "2") (pinfunction "2_2") (pintype "passive"))
    )
    (net (code "5") (name "/C4") (class "Default")
      (node (ref "D2") (pin "1") (pinfunction "A_1") (pintype "passive"))
      (node (ref "D3") (pin "2") (pinfunction "K_2") (pintype "passive"))
      (node (ref "R16") (pin "2") (pinfunction "2_2") (pintype "passive"))
    )
    (net (code "6") (name "/C5") (class "Default")
      (node (ref "D1") (pin "1") (pinfunction "A_1") (pintype "passive"))
      (node (ref "D2") (pin "2") (pinfunction "K_2") (pintype "passive"))
      (node (ref "R15") (pin "2") (pinfunction "2_2") (pintype "passive"))
    )
    (net (code "7") (name "/C6") (class "Default")
      (node (ref "D1") (pin "2") (pinfunction "K_2") (pintype "passive"))
      (node (ref "D12") (pin "1") (pinfunction "A_1") (pintype "passive"))
      (node (ref "R14") (pin "2") (pinfunction "2_2") (pintype "passive"))
    )
    (net (code "8") (name "/C7") (class "Default")
      (node (ref "D11") (pin "1") (pinfunction "A_1") (pintype "passive"))
      (node (ref "D12") (pin "2") (pinfunction "K_2") (pintype "passive"))
      (node (ref "R43") (pin "2") (pinfunction "2_2") (pintype "passive"))
    )
    (net (code "9") (name "/C8") (class "Default")
      (node (ref "D10") (pin "1") (pinfunction "A_1") (pintype "passive"))
      (node (ref "D11") (pin "2") (pinfunction "K_2") (pintype "passive"))
      (node (ref "R42") (pin "2") (pinfunction "2_2") (pintype "passive"))
    )
    (net (code "10") (name "/C9") (class "Default")
      (node (ref "D10") (pin "2") (pinfunction "K_2") (pintype "passive"))
      (node (ref "D9") (pin "1") (pinfunction "A_1") (pintype "passive"))
      (node (ref "R41") (pin "2") (pinfunction "2_2") (pintype "passive"))
    )
    (net (code "11") (name "/C10") (class "Default")
      (node (ref "D8") (pin "1") (pinfunction "A_1") (pintype "passive"))
      (node (ref "D9") (pin "2") (pinfunction "K_2") (pintype "passive"))
      (node (ref "R40") (pin "2") (pinfunction "2_2") (pintype "passive"))
    )
    (net (code "12") (name "/C11") (class "Default")
      (node (ref "D7") (pin "1") (pinfunction "A_1") (pintype "passive"))
      (node (ref "D8") (pin "2") (pinfunction "K_2") (pintype "passive"))
      (node (ref "R39") (pin "2") (pinfunction "2_2") (pintype "passive"))
    )
    (net (code "13") (name "/C12") (class "Default")
      (node (ref "D14") (pin "1") (pinfunction "A_1") (pintype "passive"))
      (node (ref "D7") (pin "2") (pinfunction "K_2") (pintype "passive"))
      (node (ref "R38") (pin "2") (pinfunction "2_2") (pintype "passive"))
    )
    (net (code "14") (name "/C13") (class "Default")
      (node (ref "D13") (pin "1") (pinfunction "A_1") (pintype "passive"))
      (node (ref "D14") (pin "2") (pinfunction "K_2") (pintype "passive"))
      (node (ref "R55") (pin "2") (pinfunction "2_2") (pintype "passive"))
    )
    (net (code "15") (name "/C14") (class "Default")
      (node (ref "D13") (pin "2") (pinfunction "K_2") (pintype "passive"))
      (node (ref "R54") (pin "2") (pinfunction "2_2") (pintype "passive"))
    )
    (net (code "16") (name "/CELL1") (class "Default")
      (node (ref "DS5") (pin "2") (pinfunction "K_2") (pintype "passive"))
      (node (ref "Q6") (pin "2") (pinfunction "SOURCE_2") (pintype "passive"))
      (node (ref "R11") (pin "1") (pinfunction "1_1") (pintype "passive"))
      (node (ref "R19") (pin "1") (pinfunction "1_1") (pintype "passive"))
    )
    (net (code "17") (name "/CELL2") (class "Default")
      (node (ref "DS4") (pin "2") (pinfunction "K_2") (pintype "passive"))
      (node (ref "Q5") (pin "2") (pinfunction "SOURCE_2") (pintype "passive"))
      (node (ref "R10") (pin "1") (pinfunction "1_1") (pintype "passive"))
      (node (ref "R18") (pin "1") (pinfunction "1_1") (pintype "passive"))
    )
    (net (code "18") (name "/CELL3") (class "Default")
      (node (ref "DS3") (pin "2") (pinfunction "K_2") (pintype "passive"))
      (node (ref "Q4") (pin "2") (pinfunction "SOURCE_2") (pintype "passive"))
      (node (ref "R17") (pin "1") (pinfunction "1_1") (pintype "passive"))
      (node (ref "R9") (pin "1") (pinfunction "1_1") (pintype "passive"))
    )
    (net (code "19") (name "/CELL4") (class "Default")
      (node (ref "DS2") (pin "2") (pinfunction "K_2") (pintype "passive"))
      (node (ref "Q3") (pin "2") (pinfunction "SOURCE_2") (pintype "passive"))
      (node (ref "R16") (pin "1") (pinfunction "1_1") (pintype "passive"))
      (node (ref "R8") (pin "1") (pinfunction "1_1") (pintype "passive"))
    )
    (net (code "20") (name "/CELL5") (class "Default")
      (node (ref "DS1") (pin "2") (pinfunction "K_2") (pintype "passive"))
      (node (ref "Q2") (pin "2") (pinfunction "SOURCE_2") (pintype "passive"))
      (node (ref "R15") (pin "1") (pinfunction "1_1") (pintype "passive"))
      (node (ref "R7") (pin "1") (pinfunction "1_1") (pintype "passive"))
    )
    (net (code "21") (name "/CELL6") (class "Default")
      (node (ref "DS12") (pin "2") (pinfunction "K_2") (pintype "passive"))
      (node (ref "Q1") (pin "2") (pinfunction "SOURCE_2") (pintype "passive"))
      (node (ref "R14") (pin "1") (pinfunction "1_1") (pintype "passive"))
      (node (ref "R37") (pin "1") (pinfunction "1_1") (pintype "passive"))
    )
    (net (code "22") (name "/CELL7") (class "Default")
      (node (ref "DS11") (pin "2") (pinfunction "K_2") (pintype "passive"))
      (node (ref "Q12") (pin "2") (pinfunction "SOURCE_2") (pintype "passive"))
      (node (ref "R36") (pin "1") (pinfunction "1_1") (pintype "passive"))
      (node (ref "R43") (pin "1") (pinfunction "1_1") (pintype "passive"))
    )
    (net (code "23") (name "/CELL8") (class "Default")
      (node (ref "DS10") (pin "2") (pinfunction "K_2") (pintype "passive"))
      (node (ref "Q11") (pin "2") (pinfunction "SOURCE_2") (pintype "passive"))
      (node (ref "R35") (pin "1") (pinfunction "1_1") (pintype "passive"))
      (node (ref "R42") (pin "1") (pinfunction "1_1") (pintype "passive"))
    )
    (net (code "24") (name "/CELL9") (class "Default")
      (node (ref "DS9") (pin "2") (pinfunction "K_2") (pintype "passive"))
      (node (ref "Q10") (pin "2") (pinfunction "SOURCE_2") (pintype "passive"))
      (node (ref "R34") (pin "1") (pinfunction "1_1") (pintype "passive"))
      (node (ref "R41") (pin "1") (pinfunction "1_1") (pintype "passive"))
    )
    (net (code "25") (name "/CELL10") (class "Default")
      (node (ref "DS8") (pin "2") (pinfunction "K_2") (pintype "passive"))
      (node (ref "Q9") (pin "2") (pinfunction "SOURCE_2") (pintype "passive"))
      (node (ref "R33") (pin "1") (pinfunction "1_1") (pintype "passive"))
      (node (ref "R40") (pin "1") (pinfunction "1_1") (pintype "passive"))
    )
    (net (code "26") (name "/CELL11") (class "Default")
      (node (ref "DS7") (pin "2") (pinfunction "K_2") (pintype "passive"))
      (node (ref "Q8") (pin "2") (pinfunction "SOURCE_2") (pintype "passive"))
      (node (ref "R32") (pin "1") (pinfunction "1_1") (pintype "passive"))
      (node (ref "R39") (pin "1") (pinfunction "1_1") (pintype "passive"))
    )
    (net (code "27") (name "/CELL12") (class "Default")
      (node (ref "DS14") (pin "2") (pinfunction "K_2") (pintype "passive"))
      (node (ref "Q7") (pin "2") (pinfunction "SOURCE_2") (pintype "passive"))
      (node (ref "R38") (pin "1") (pinfunction "1_1") (pintype "passive"))
      (node (ref "R53") (pin "1") (pinfunction "1_1") (pintype "passive"))
    )
    (net (code "28") (name "/CELL13") (class "Default")
      (node (ref "DS13") (pin "2") (pinfunction "K_2") (pintype "passive"))
      (node (ref "Q14") (pin "2") (pinfunction "SOURCE_2") (pintype "passive"))
      (node (ref "R52") (pin "1") (pinfunction "1_1") (pintype "passive"))
      (node (ref "R55") (pin "1") (pinfunction "1_1") (pintype "passive"))
    )
    (net (code "29") (name "/CELL14") (class "Default")
      (node (ref "Q13") (pin "2") (pinfunction "SOURCE_2") (pintype "passive"))
      (node (ref "R54") (pin "1") (pinfunction "1_1") (pintype "passive"))
    )
    (net (code "30") (name "/S1") (class "Default")
      (node (ref "C7") (pin "2") (pinfunction "2_2") (pintype "passive"))
      (node (ref "R26") (pin "2") (pinfunction "2_2") (pintype "passive"))
    )
    (net (code "31") (name "/S2") (class "Default")
      (node (ref "C12") (pin "2") (pinfunction "2_2") (pintype "passive"))
      (node (ref "R25") (pin "2") (pinfunction "2_2") (pintype "passive"))
    )
    (net (code "32") (name "/S3") (class "Default")
      (node (ref "C11") (pin "2") (pinfunction "2_2") (pintype "passive"))
      (node (ref "R24") (pin "2") (pinfunction "2_2") (pintype "passive"))
    )
    (net (code "33") (name "/S4") (class "Default")
      (node (ref "C10") (pin "2") (pinfunction "2_2") (pintype "passive"))
      (node (ref "R23") (pin "2") (pinfunction "2_2") (pintype "passive"))
    )
    (net (code "34") (name "/S5") (class "Default")
      (node (ref "C9") (pin "2") (pinfunction "2_2") (pintype "passive"))
      (node (ref "R22") (pin "2") (pinfunction "2_2") (pintype "passive"))
    )
    (net (code "35") (name "/S6") (class "Default")
      (node (ref "C8") (pin "2") (pinfunction "2_2") (pintype "passive"))
      (node (ref "R21") (pin "2") (pinfunction "2_2") (pintype "passive"))
    )
    (net (code "36") (name "/S7") (class "Default")
      (node (ref "C18") (pin "2") (pinfunction "2_2") (pintype "passive"))
      (node (ref "R50") (pin "2") (pinfunction "2_2") (pintype "passive"))
    )
    (net (code "37") (name "/S8") (class "Default")
      (node (ref "C17") (pin "2") (pinfunction "2_2") (pintype "passive"))
      (node (ref "R49") (pin "2") (pinfunction "2_2") (pintype "passive"))
    )
    (net (code "38") (name "/S9") (class "Default")
      (node (ref "C16") (pin "2") (pinfunction "2_2") (pintype "passive"))
      (node (ref "R48") (pin "2") (pinfunction "2_2") (pintype "passive"))
    )
    (net (code "39") (name "/S10") (class "Default")
      (node (ref "C15") (pin "2") (pinfunction "2_2") (pintype "passive"))
      (node (ref "R47") (pin "2") (pinfunction "2_2") (pintype "passive"))
    )
    (net (code "40") (name "/S11") (class "Default")
      (node (ref "C14") (pin "2") (pinfunction "2_2") (pintype "passive"))
      (node (ref "R46") (pin "2") (pinfunction "2_2") (pintype "passive"))
    )
    (net (code "41") (name "/S12") (class "Default")
      (node (ref "C13") (pin "2") (pinfunction "2_2") (pintype "passive"))
      (node (ref "R45") (pin "2") (pinfunction "2_2") (pintype "passive"))
    )
    (net (code "42") (name "/S13") (class "Default")
      (node (ref "C20") (pin "2") (pinfunction "2_2") (pintype "passive"))
      (node (ref "R58") (pin "2") (pinfunction "2_2") (pintype "passive"))
    )
    (net (code "43") (name "/S14") (class "Default")
      (node (ref "C19") (pin "2") (pinfunction "2_2") (pintype "passive"))
      (node (ref "R57") (pin "2") (pinfunction "2_2") (pintype "passive"))
    )
    (net (code "44") (name "GND") (class "Default")
      (node (ref "C10") (pin "1") (pinfunction "1_1") (pintype "passive"))
      (node (ref "C11") (pin "1") (pinfunction "1_1") (pintype "passive"))
      (node (ref "C12") (pin "1") (pinfunction "1_1") (pintype "passive"))
      (node (ref "C13") (pin "1") (pinfunction "1_1") (pintype "passive"))
      (node (ref "C14") (pin "1") (pinfunction "1_1") (pintype "passive"))
      (node (ref "C15") (pin "1") (pinfunction "1_1") (pintype "passive"))
      (node (ref "C16") (pin "1") (pinfunction "1_1") (pintype "passive"))
      (node (ref "C17") (pin "1") (pinfunction "1_1") (pintype "passive"))
      (node (ref "C18") (pin "1") (pinfunction "1_1") (pintype "passive"))
      (node (ref "C19") (pin "1") (pinfunction "1_1") (pintype "passive"))
      (node (ref "C20") (pin "1") (pinfunction "1_1") (pintype "passive"))
      (node (ref "C6") (pin "1") (pinfunction "1_1") (pintype "passive"))
      (node (ref "C7") (pin "1") (pinfunction "1_1") (pintype "passive"))
      (node (ref "C8") (pin "1") (pinfunction "1_1") (pintype "passive"))
      (node (ref "C9") (pin "1") (pinfunction "1_1") (pintype "passive"))
    )
    (net (code "45") (name "Net-(DS1-A)") (class "Default")
      (node (ref "DS1") (pin "1") (pinfunction "A_1") (pintype "passive"))
      (node (ref "R2") (pin "1") (pinfunction "1_1") (pintype "passive"))
    )
    (net (code "46") (name "Net-(DS2-A)") (class "Default")
      (node (ref "DS2") (pin "1") (pinfunction "A_1") (pintype "passive"))
      (node (ref "R3") (pin "1") (pinfunction "1_1") (pintype "passive"))
    )
    (net (code "47") (name "Net-(DS3-A)") (class "Default")
      (node (ref "DS3") (pin "1") (pinfunction "A_1") (pintype "passive"))
      (node (ref "R4") (pin "1") (pinfunction "1_1") (pintype "passive"))
    )
    (net (code "48") (name "Net-(DS4-A)") (class "Default")
      (node (ref "DS4") (pin "1") (pinfunction "A_1") (pintype "passive"))
      (node (ref "R5") (pin "1") (pinfunction "1_1") (pintype "passive"))
    )
    (net (code "49") (name "Net-(DS5-A)") (class "Default")
      (node (ref "DS5") (pin "1") (pinfunction "A_1") (pintype "passive"))
      (node (ref "R6") (pin "1") (pinfunction "1_1") (pintype "passive"))
    )
    (net (code "50") (name "Net-(DS6-A)") (class "Default")
      (node (ref "DS6") (pin "1") (pinfunction "A_1") (pintype "passive"))
      (node (ref "R20") (pin "1") (pinfunction "1_1") (pintype "passive"))
    )
    (net (code "51") (name "Net-(DS6-K)") (class "Default")
      (node (ref "DS6") (pin "2") (pinfunction "K_2") (pintype "passive"))
      (node (ref "R12") (pin "1") (pinfunction "1_1") (pintype "passive"))
      (node (ref "R13") (pin "1") (pinfunction "1_1") (pintype "passive"))
    )
    (net (code "52") (name "Net-(DS7-A)") (class "Default")
      (node (ref "DS7") (pin "1") (pinfunction "A_1") (pintype "passive"))
      (node (ref "R27") (pin "1") (pinfunction "1_1") (pintype "passive"))
    )
    (net (code "53") (name "Net-(DS8-A)") (class "Default")
      (node (ref "DS8") (pin "1") (pinfunction "A_1") (pintype "passive"))
      (node (ref "R28") (pin "1") (pinfunction "1_1") (pintype "passive"))
    )
    (net (code "54") (name "Net-(DS9-A)") (class "Default")
      (node (ref "DS9") (pin "1") (pinfunction "A_1") (pintype "passive"))
      (node (ref "R29") (pin "1") (pinfunction "1_1") (pintype "passive"))
    )
    (net (code "55") (name "Net-(DS10-A)") (class "Default")
      (node (ref "DS10") (pin "1") (pinfunction "A_1") (pintype "passive"))
      (node (ref "R30") (pin "1") (pinfunction "1_1") (pintype "passive"))
    )
    (net (code "56") (name "Net-(DS11-A)") (class "Default")
      (node (ref "DS11") (pin "1") (pinfunction "A_1") (pintype "passive"))
      (node (ref "R31") (pin "1") (pinfunction "1_1") (pintype "passive"))
    )
    (net (code "57") (name "Net-(DS12-A)") (class "Default")
      (node (ref "DS12") (pin "1") (pinfunction "A_1") (pintype "passive"))
      (node (ref "R44") (pin "1") (pinfunction "1_1") (pintype "passive"))
    )
    (net (code "58") (name "Net-(DS13-A)") (class "Default")
      (node (ref "DS13") (pin "1") (pinfunction "A_1") (pintype "passive"))
      (node (ref "R51") (pin "1") (pinfunction "1_1") (pintype "passive"))
    )
    (net (code "59") (name "Net-(DS14-A)") (class "Default")
      (node (ref "DS14") (pin "1") (pinfunction "A_1") (pintype "passive"))
      (node (ref "R56") (pin "1") (pinfunction "1_1") (pintype "passive"))
    )
    (net (code "60") (name "Net-(Q1-DRAIN)") (class "Default")
      (node (ref "Q1") (pin "3") (pinfunction "DRAIN_3") (pintype "passive"))
      (node (ref "R2") (pin "2") (pinfunction "2_2") (pintype "passive"))
      (node (ref "R7") (pin "2") (pinfunction "2_2") (pintype "passive"))
    )
    (net (code "61") (name "Net-(Q1-GATE)") (class "Default")
      (node (ref "Q1") (pin "1") (pinfunction "GATE_1") (pintype "passive"))
      (node (ref "R21") (pin "1") (pinfunction "1_1") (pintype "passive"))
    )
    (net (code "62") (name "Net-(Q2-DRAIN)") (class "Default")
      (node (ref "Q2") (pin "3") (pinfunction "DRAIN_3") (pintype "passive"))
      (node (ref "R3") (pin "2") (pinfunction "2_2") (pintype "passive"))
      (node (ref "R8") (pin "2") (pinfunction "2_2") (pintype "passive"))
    )
    (net (code "63") (name "Net-(Q2-GATE)") (class "Default")
      (node (ref "Q2") (pin "1") (pinfunction "GATE_1") (pintype "passive"))
      (node (ref "R22") (pin "1") (pinfunction "1_1") (pintype "passive"))
    )
    (net (code "64") (name "Net-(Q3-DRAIN)") (class "Default")
      (node (ref "Q3") (pin "3") (pinfunction "DRAIN_3") (pintype "passive"))
      (node (ref "R4") (pin "2") (pinfunction "2_2") (pintype "passive"))
      (node (ref "R9") (pin "2") (pinfunction "2_2") (pintype "passive"))
    )
    (net (code "65") (name "Net-(Q3-GATE)") (class "Default")
      (node (ref "Q3") (pin "1") (pinfunction "GATE_1") (pintype "passive"))
      (node (ref "R23") (pin "1") (pinfunction "1_1") (pintype "passive"))
    )
    (net (code "66") (name "Net-(Q4-DRAIN)") (class "Default")
      (node (ref "Q4") (pin "3") (pinfunction "DRAIN_3") (pintype "passive"))
      (node (ref "R10") (pin "2") (pinfunction "2_2") (pintype "passive"))
      (node (ref "R5") (pin "2") (pinfunction "2_2") (pintype "passive"))
    )
    (net (code "67") (name "Net-(Q4-GATE)") (class "Default")
      (node (ref "Q4") (pin "1") (pinfunction "GATE_1") (pintype "passive"))
      (node (ref "R24") (pin "1") (pinfunction "1_1") (pintype "passive"))
    )
    (net (code "68") (name "Net-(Q5-DRAIN)") (class "Default")
      (node (ref "Q5") (pin "3") (pinfunction "DRAIN_3") (pintype "passive"))
      (node (ref "R11") (pin "2") (pinfunction "2_2") (pintype "passive"))
      (node (ref "R6") (pin "2") (pinfunction "2_2") (pintype "passive"))
    )
    (net (code "69") (name "Net-(Q5-GATE)") (class "Default")
      (node (ref "Q5") (pin "1") (pinfunction "GATE_1") (pintype "passive"))
      (node (ref "R25") (pin "1") (pinfunction "1_1") (pintype "passive"))
    )
    (net (code "70") (name "Net-(Q6-DRAIN)") (class "Default")
      (node (ref "Q6") (pin "3") (pinfunction "DRAIN_3") (pintype "passive"))
      (node (ref "R12") (pin "2") (pinfunction "2_2") (pintype "passive"))
      (node (ref "R20") (pin "2") (pinfunction "2_2") (pintype "passive"))
    )
    (net (code "71") (name "Net-(Q6-GATE)") (class "Default")
      (node (ref "Q6") (pin "1") (pinfunction "GATE_1") (pintype "passive"))
      (node (ref "R26") (pin "1") (pinfunction "1_1") (pintype "passive"))
    )
    (net (code "72") (name "Net-(Q7-DRAIN)") (class "Default")
      (node (ref "Q7") (pin "3") (pinfunction "DRAIN_3") (pintype "passive"))
      (node (ref "R27") (pin "2") (pinfunction "2_2") (pintype "passive"))
      (node (ref "R32") (pin "2") (pinfunction "2_2") (pintype "passive"))
    )
    (net (code "73") (name "Net-(Q7-GATE)") (class "Default")
      (node (ref "Q7") (pin "1") (pinfunction "GATE_1") (pintype "passive"))
      (node (ref "R45") (pin "1") (pinfunction "1_1") (pintype "passive"))
    )
    (net (code "74") (name "Net-(Q8-DRAIN)") (class "Default")
      (node (ref "Q8") (pin "3") (pinfunction "DRAIN_3") (pintype "passive"))
      (node (ref "R28") (pin "2") (pinfunction "2_2") (pintype "passive"))
      (node (ref "R33") (pin "2") (pinfunction "2_2") (pintype "passive"))
    )
    (net (code "75") (name "Net-(Q8-GATE)") (class "Default")
      (node (ref "Q8") (pin "1") (pinfunction "GATE_1") (pintype "passive"))
      (node (ref "R46") (pin "1") (pinfunction "1_1") (pintype "passive"))
    )
    (net (code "76") (name "Net-(Q9-DRAIN)") (class "Default")
      (node (ref "Q9") (pin "3") (pinfunction "DRAIN_3") (pintype "passive"))
      (node (ref "R29") (pin "2") (pinfunction "2_2") (pintype "passive"))
      (node (ref "R34") (pin "2") (pinfunction "2_2") (pintype "passive"))
    )
    (net (code "77") (name "Net-(Q9-GATE)") (class "Default")
      (node (ref "Q9") (pin "1") (pinfunction "GATE_1") (pintype "passive"))
      (node (ref "R47") (pin "1") (pinfunction "1_1") (pintype "passive"))
    )
    (net (code "78") (name "Net-(Q10-DRAIN)") (class "Default")
      (node (ref "Q10") (pin "3") (pinfunction "DRAIN_3") (pintype "passive"))
      (node (ref "R30") (pin "2") (pinfunction "2_2") (pintype "passive"))
      (node (ref "R35") (pin "2") (pinfunction "2_2") (pintype "passive"))
    )
    (net (code "79") (name "Net-(Q10-GATE)") (class "Default")
      (node (ref "Q10") (pin "1") (pinfunction "GATE_1") (pintype "passive"))
      (node (ref "R48") (pin "1") (pinfunction "1_1") (pintype "passive"))
    )
    (net (code "80") (name "Net-(Q11-DRAIN)") (class "Default")
      (node (ref "Q11") (pin "3") (pinfunction "DRAIN_3") (pintype "passive"))
      (node (ref "R31") (pin "2") (pinfunction "2_2") (pintype "passive"))
      (node (ref "R36") (pin "2") (pinfunction "2_2") (pintype "passive"))
    )
    (net (code "81") (name "Net-(Q11-GATE)") (class "Default")
      (node (ref "Q11") (pin "1") (pinfunction "GATE_1") (pintype "passive"))
      (node (ref "R49") (pin "1") (pinfunction "1_1") (pintype "passive"))
    )
    (net (code "82") (name "Net-(Q12-DRAIN)") (class "Default")
      (node (ref "Q12") (pin "3") (pinfunction "DRAIN_3") (pintype "passive"))
      (node (ref "R37") (pin "2") (pinfunction "2_2") (pintype "passive"))
      (node (ref "R44") (pin "2") (pinfunction "2_2") (pintype "passive"))
    )
    (net (code "83") (name "Net-(Q12-GATE)") (class "Default")
      (node (ref "Q12") (pin "1") (pinfunction "GATE_1") (pintype "passive"))
      (node (ref "R50") (pin "1") (pinfunction "1_1") (pintype "passive"))
    )
    (net (code "84") (name "Net-(Q13-DRAIN)") (class "Default")
      (node (ref "Q13") (pin "3") (pinfunction "DRAIN_3") (pintype "passive"))
      (node (ref "R51") (pin "2") (pinfunction "2_2") (pintype "passive"))
      (node (ref "R52") (pin "2") (pinfunction "2_2") (pintype "passive"))
    )
    (net (code "85") (name "Net-(Q13-GATE)") (class "Default")
      (node (ref "Q13") (pin "1") (pinfunction "GATE_1") (pintype "passive"))
      (node (ref "R57") (pin "1") (pinfunction "1_1") (pintype "passive"))
    )
    (net (code "86") (name "Net-(Q14-DRAIN)") (class "Default")
      (node (ref "Q14") (pin "3") (pinfunction "DRAIN_3") (pintype "passive"))
      (node (ref "R53") (pin "2") (pinfunction "2_2") (pintype "passive"))
      (node (ref "R56") (pin "2") (pinfunction "2_2") (pintype "passive"))
    )
    (net (code "87") (name "Net-(Q14-GATE)") (class "Default")
      (node (ref "Q14") (pin "1") (pinfunction "GATE_1") (pintype "passive"))
      (node (ref "R58") (pin "1") (pinfunction "1_1") (pintype "passive"))
    )
  )
)
